# Schematic.net
KiCad netlist of a schematic drawn in EasyEDA
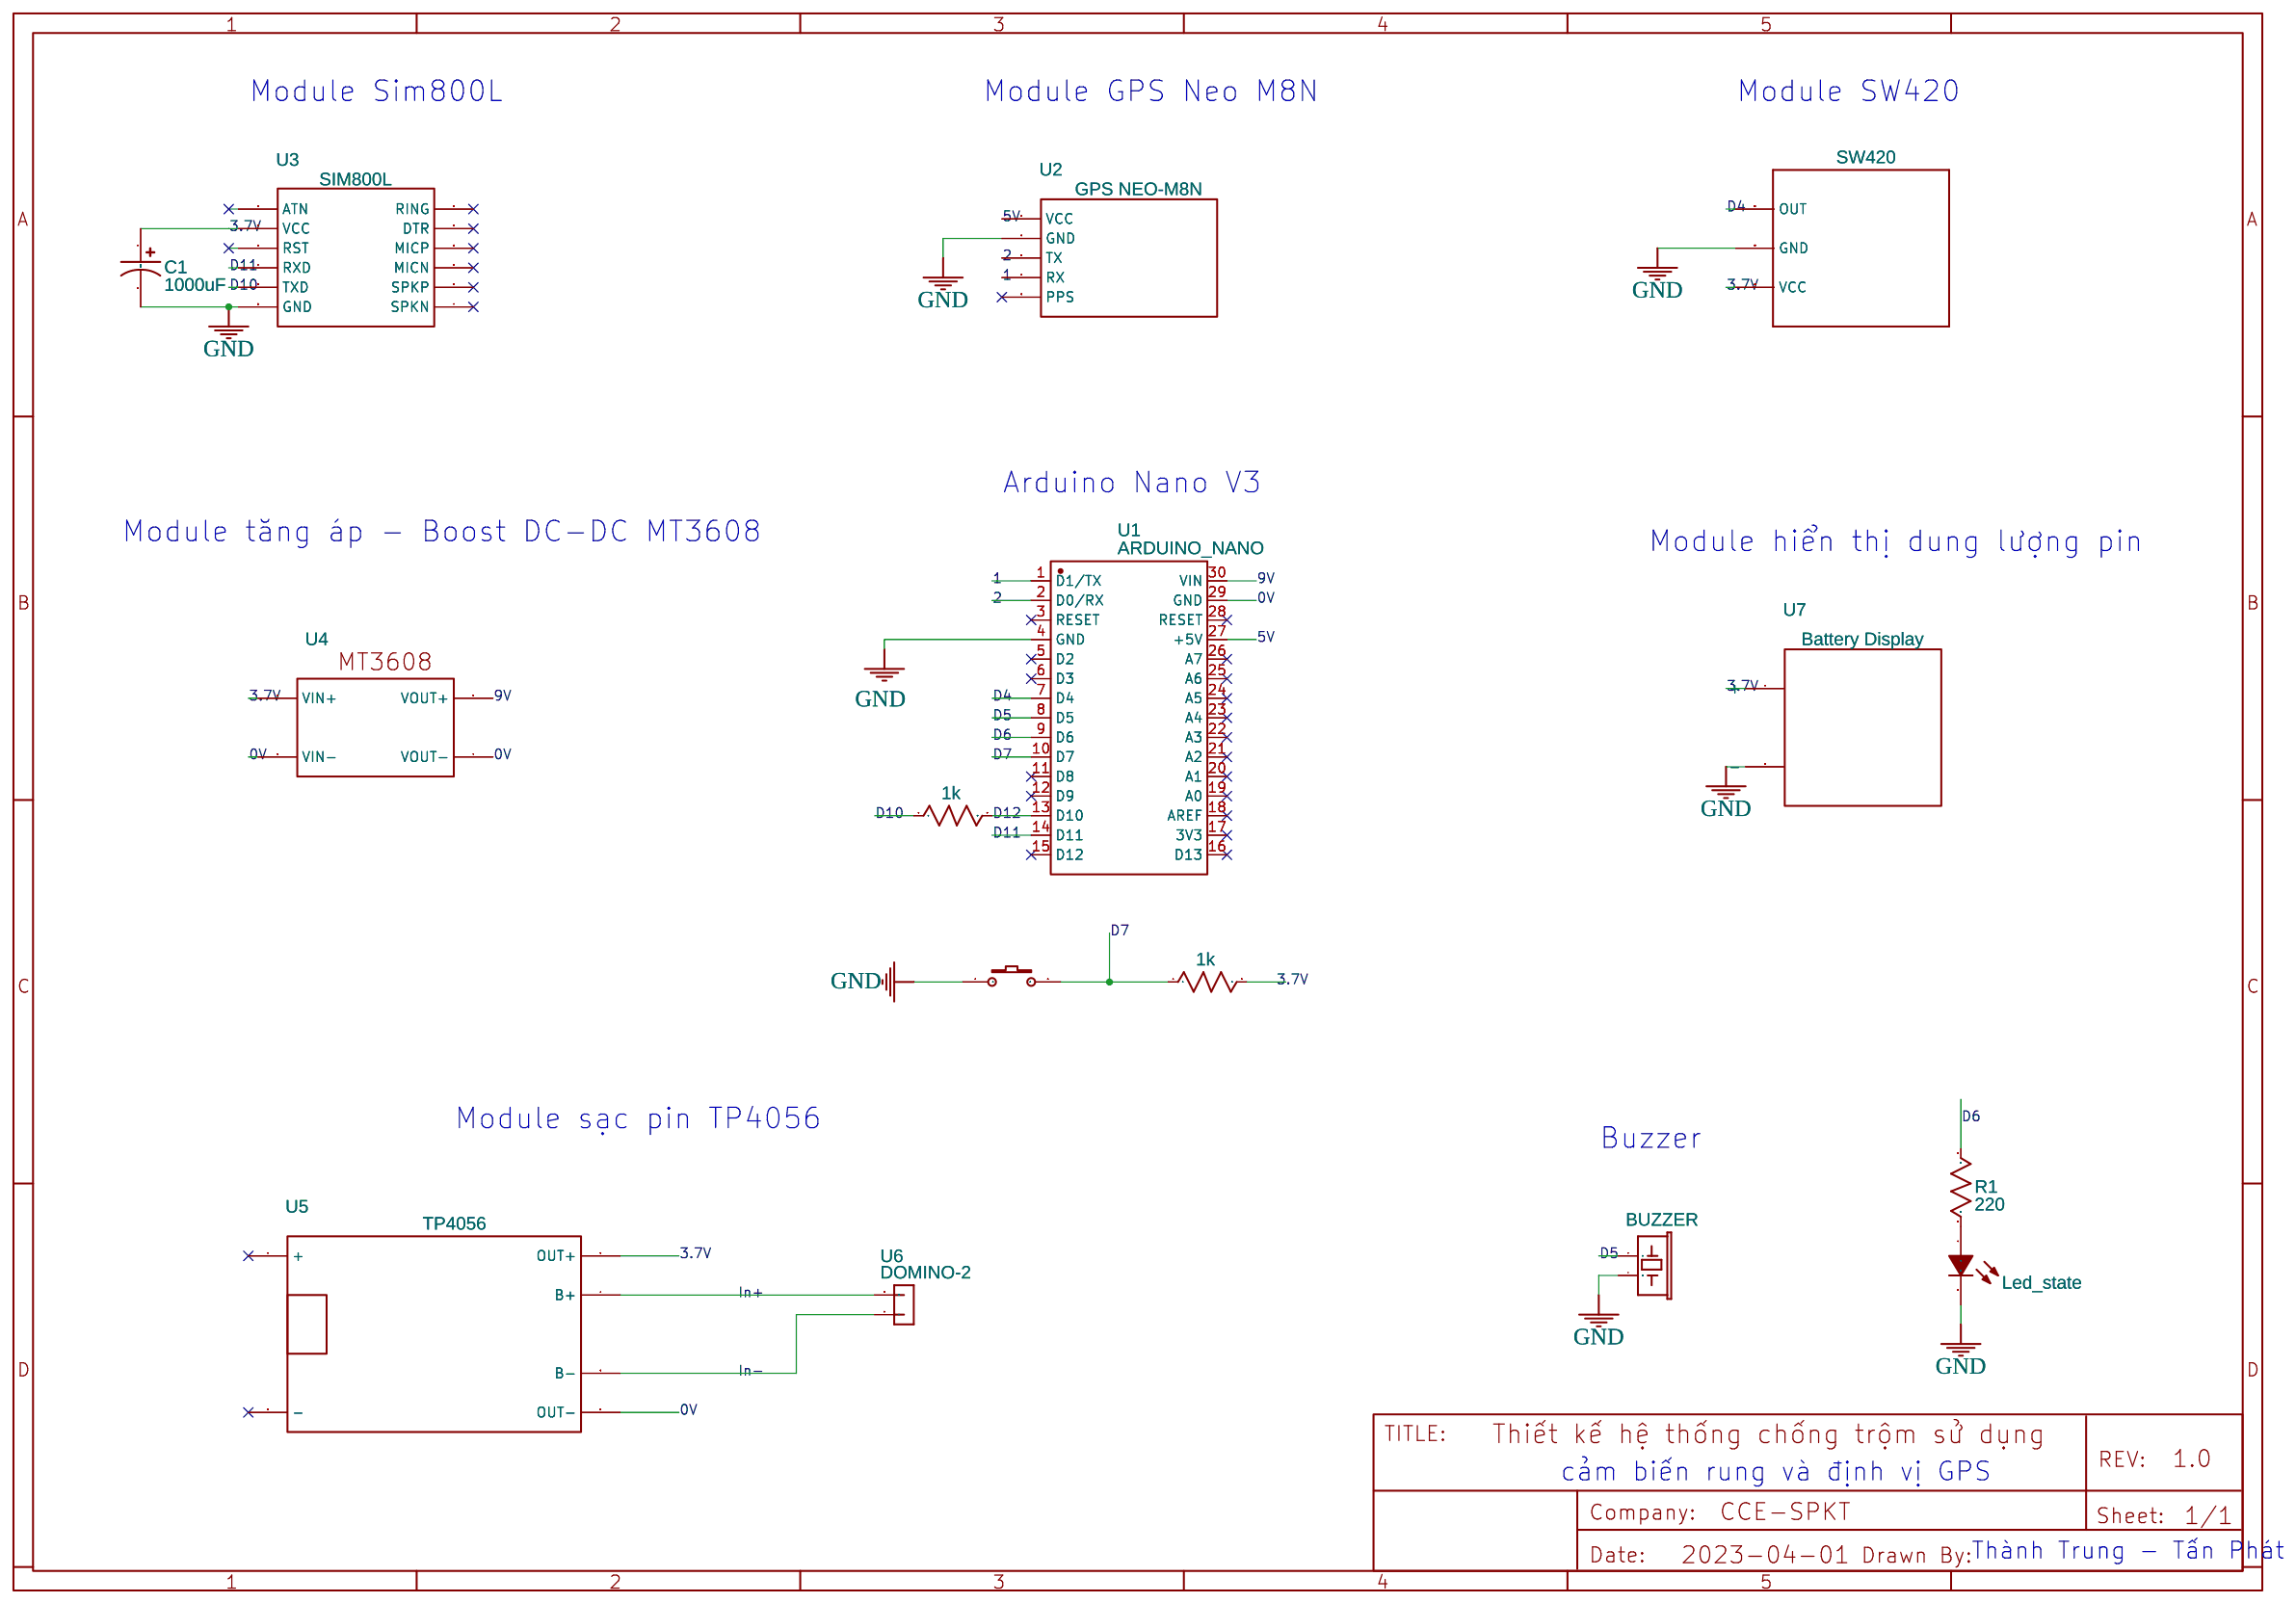
[diagram p0: schematic sheet]

(export (version "E")
  (design (tool "Eeschema 10.0.6"))
  (components
    (comp (ref "1") (value "SW420") (libsource (lib "") (part "SW420")))
    (comp (ref "C1")
      (value "1000uF")
      (fields
        (field (name "BOM_Manufacturer Part") "SHW1000UF6.3V6.3X11")
        (field (name "BOM_Supplier Part") "C494544")
      )
      (libsource (lib "") (part "SHW1000UF6.3V6.3X11"))
    )
    (comp (ref "KEY1")
      (value "K2-3.6×6.1_SMD")
      (fields
        (field (name "BOM_Manufacturer Part") "K2-1107ST-A4SW-06")
        (field (name "BOM_Supplier Part") "C118141")
      )
      (libsource (lib "") (part "K2-3.6×6.1_SMD"))
    )
    (comp (ref "LED1")
      (value "Led_state")
      (fields
        (field (name "BOM_Manufacturer Part") "LED_5MM")
        (field (name "BOM_Supplier Part") "C9900023552")
      )
      (libsource (lib "") (part "LED_5MM"))
    )
    (comp (ref "R1") (value "220") (libsource (lib "") (part "R_0603_US")))
    (comp (ref "R2") (value "1k") (libsource (lib "") (part "R_0603_US_1")))
    (comp (ref "R3") (value "1k") (libsource (lib "") (part "R_0603_US_1")))
    (comp (ref "SG1") (value "BUZZER") (libsource (lib "") (part "BUZZERPTH-NS-KIT")))
    (comp (ref "U1")
      (value "ARDUINO_NANO")
      (fields (field (name "BOM_Supplier Part") "C9900017879"))
      (libsource (lib "") (part "ARDUINO_NANO"))
    )
    (comp (ref "U2") (value "GPS NEO-M8N") (libsource (lib "") (part "NEO-M8N Double Sided GPS Mini Module")))
    (comp (ref "U3") (value "SIM800L") (libsource (lib "") (part "SIM800L_MODULE")))
    (comp (ref "U4") (value "MT3608") (libsource (lib "") (part "MT3608")))
    (comp (ref "U5") (value "TP4056") (libsource (lib "") (part "TP4056 MODULE")))
    (comp (ref "U6") (value "DOMINO-2") (libsource (lib "") (part "DOMINO-2")))
    (comp (ref "U7")
      (value "Battery Display")
      (fields (field (name "BOM_Manufacturer Part") "540-563"))
      (libsource (lib "") (part "báo pin"))
    )
  )
  (nets
    (net (code "1") (name "/0V") (class "Default")
      (node (ref "U1") (pin "29") (pinfunction "GND_29") (pintype "unspecified"))
      (node (ref "U4") (pin "2") (pinfunction "VIN-_2") (pintype "unspecified"))
      (node (ref "U4") (pin "4") (pinfunction "VOUT-_4") (pintype "unspecified"))
      (node (ref "U5") (pin "6") (pinfunction "OUT-_6") (pintype "unspecified"))
    )
    (net (code "2") (name "/1") (class "Default")
      (node (ref "U1") (pin "1") (pinfunction "D1/TX_1") (pintype "unspecified"))
      (node (ref "U2") (pin "4") (pinfunction "RX_4") (pintype "unspecified"))
    )
    (net (code "3") (name "/2") (class "Default")
      (node (ref "U1") (pin "2") (pinfunction "D0/RX_2") (pintype "unspecified"))
      (node (ref "U2") (pin "3") (pinfunction "TX_3") (pintype "unspecified"))
    )
    (net (code "4") (name "/3.7V") (class "Default")
      (node (ref "1") (pin "VCC") (pinfunction "VCC_VCC") (pintype "bidirectional"))
      (node (ref "C1") (pin "1") (pinfunction "1_1") (pintype "unspecified"))
      (node (ref "R2") (pin "2") (pinfunction "2_2") (pintype "unspecified"))
      (node (ref "U3") (pin "2") (pinfunction "VCC_2") (pintype "unspecified"))
      (node (ref "U4") (pin "1") (pinfunction "VIN+_1") (pintype "unspecified"))
      (node (ref "U5") (pin "3") (pinfunction "OUT+_3") (pintype "unspecified"))
      (node (ref "U7") (pin "1") (pinfunction "+_1") (pintype "unspecified"))
    )
    (net (code "5") (name "/5V") (class "Default")
      (node (ref "U1") (pin "27") (pinfunction "+5V_27") (pintype "unspecified"))
      (node (ref "U2") (pin "1") (pinfunction "VCC_1") (pintype "unspecified"))
    )
    (net (code "6") (name "/9V") (class "Default")
      (node (ref "U1") (pin "30") (pinfunction "VIN_30") (pintype "unspecified"))
      (node (ref "U4") (pin "3") (pinfunction "VOUT+_3") (pintype "unspecified"))
    )
    (net (code "7") (name "/D4") (class "Default")
      (node (ref "1") (pin "OUT") (pinfunction "OUT_OUT") (pintype "bidirectional"))
      (node (ref "U1") (pin "7") (pinfunction "D4_7") (pintype "unspecified"))
    )
    (net (code "8") (name "/D5") (class "Default")
      (node (ref "SG1") (pin "+") (pinfunction "1_+") (pintype "unspecified"))
      (node (ref "U1") (pin "8") (pinfunction "D5_8") (pintype "unspecified"))
    )
    (net (code "9") (name "/D6") (class "Default")
      (node (ref "R1") (pin "1") (pinfunction "1_1") (pintype "unspecified"))
      (node (ref "U1") (pin "9") (pinfunction "D6_9") (pintype "unspecified"))
    )
    (net (code "10") (name "/D7") (class "Default")
      (node (ref "KEY1") (pin "2") (pinfunction "2_2") (pintype "unspecified"))
      (node (ref "R2") (pin "1") (pinfunction "1_1") (pintype "unspecified"))
      (node (ref "U1") (pin "10") (pinfunction "D7_10") (pintype "unspecified"))
    )
    (net (code "11") (name "/D10") (class "Default")
      (node (ref "R3") (pin "1") (pinfunction "1_1") (pintype "unspecified"))
      (node (ref "U3") (pin "5") (pinfunction "TXD_5") (pintype "unspecified"))
    )
    (net (code "12") (name "/D11") (class "Default")
      (node (ref "U1") (pin "14") (pinfunction "D11_14") (pintype "unspecified"))
      (node (ref "U3") (pin "4") (pinfunction "RXD_4") (pintype "unspecified"))
    )
    (net (code "13") (name "/D12") (class "Default")
      (node (ref "R3") (pin "2") (pinfunction "2_2") (pintype "unspecified"))
      (node (ref "U1") (pin "13") (pinfunction "D10_13") (pintype "unspecified"))
    )
    (net (code "14") (name "/In+") (class "Default")
      (node (ref "U5") (pin "4") (pinfunction "B+_4") (pintype "unspecified"))
      (node (ref "U6") (pin "2") (pinfunction "2_2") (pintype "unspecified"))
    )
    (net (code "15") (name "/In-") (class "Default")
      (node (ref "U5") (pin "5") (pinfunction "B-_5") (pintype "unspecified"))
      (node (ref "U6") (pin "1") (pinfunction "1_1") (pintype "unspecified"))
    )
    (net (code "16") (name "GND") (class "Default")
      (node (ref "1") (pin "GND") (pinfunction "GND_GND") (pintype "bidirectional"))
      (node (ref "C1") (pin "2") (pinfunction "2_2") (pintype "unspecified"))
      (node (ref "KEY1") (pin "1") (pinfunction "1_1") (pintype "unspecified"))
      (node (ref "LED1") (pin "2") (pinfunction "K_2") (pintype "input"))
      (node (ref "SG1") (pin "-") (pinfunction "2_-") (pintype "unspecified"))
      (node (ref "U1") (pin "4") (pinfunction "GND_4") (pintype "unspecified"))
      (node (ref "U2") (pin "2") (pinfunction "GND_2") (pintype "unspecified"))
      (node (ref "U3") (pin "6") (pinfunction "GND_6") (pintype "unspecified"))
      (node (ref "U7") (pin "2") (pinfunction "-_2") (pintype "unspecified"))
    )
    (net (code "17") (name "Net-(LED1-A)") (class "Default")
      (node (ref "LED1") (pin "1") (pinfunction "A_1") (pintype "input"))
      (node (ref "R1") (pin "2") (pinfunction "2_2") (pintype "unspecified"))
    )
    (net (code "18") (name "unconnected-(U1-3V3-Pad17)") (class "Default")
      (node (ref "U1") (pin "17") (pinfunction "3V3_17") (pintype "unspecified+no_connect"))
    )
    (net (code "19") (name "unconnected-(U1-A0-Pad19)") (class "Default")
      (node (ref "U1") (pin "19") (pinfunction "A0_19") (pintype "unspecified+no_connect"))
    )
    (net (code "20") (name "unconnected-(U1-A1-Pad20)") (class "Default")
      (node (ref "U1") (pin "20") (pinfunction "A1_20") (pintype "unspecified+no_connect"))
    )
    (net (code "21") (name "unconnected-(U1-A2-Pad21)") (class "Default")
      (node (ref "U1") (pin "21") (pinfunction "A2_21") (pintype "unspecified+no_connect"))
    )
    (net (code "22") (name "unconnected-(U1-A3-Pad22)") (class "Default")
      (node (ref "U1") (pin "22") (pinfunction "A3_22") (pintype "unspecified+no_connect"))
    )
    (net (code "23") (name "unconnected-(U1-A4-Pad23)") (class "Default")
      (node (ref "U1") (pin "23") (pinfunction "A4_23") (pintype "unspecified+no_connect"))
    )
    (net (code "24") (name "unconnected-(U1-A5-Pad24)") (class "Default")
      (node (ref "U1") (pin "24") (pinfunction "A5_24") (pintype "unspecified+no_connect"))
    )
    (net (code "25") (name "unconnected-(U1-A6-Pad25)") (class "Default")
      (node (ref "U1") (pin "25") (pinfunction "A6_25") (pintype "unspecified+no_connect"))
    )
    (net (code "26") (name "unconnected-(U1-A7-Pad26)") (class "Default")
      (node (ref "U1") (pin "26") (pinfunction "A7_26") (pintype "unspecified+no_connect"))
    )
    (net (code "27") (name "unconnected-(U1-AREF-Pad18)") (class "Default")
      (node (ref "U1") (pin "18") (pinfunction "AREF_18") (pintype "unspecified+no_connect"))
    )
    (net (code "28") (name "unconnected-(U1-D2-Pad5)") (class "Default")
      (node (ref "U1") (pin "5") (pinfunction "D2_5") (pintype "unspecified+no_connect"))
    )
    (net (code "29") (name "unconnected-(U1-D3-Pad6)") (class "Default")
      (node (ref "U1") (pin "6") (pinfunction "D3_6") (pintype "unspecified+no_connect"))
    )
    (net (code "30") (name "unconnected-(U1-D8-Pad11)") (class "Default")
      (node (ref "U1") (pin "11") (pinfunction "D8_11") (pintype "unspecified+no_connect"))
    )
    (net (code "31") (name "unconnected-(U1-D9-Pad12)") (class "Default")
      (node (ref "U1") (pin "12") (pinfunction "D9_12") (pintype "unspecified+no_connect"))
    )
    (net (code "32") (name "unconnected-(U1-D12-Pad15)") (class "Default")
      (node (ref "U1") (pin "15") (pinfunction "D12_15") (pintype "unspecified+no_connect"))
    )
    (net (code "33") (name "unconnected-(U1-D13-Pad16)") (class "Default")
      (node (ref "U1") (pin "16") (pinfunction "D13_16") (pintype "unspecified+no_connect"))
    )
    (net (code "34") (name "unconnected-(U1-RESET-Pad3)") (class "Default")
      (node (ref "U1") (pin "3") (pinfunction "RESET_3") (pintype "unspecified+no_connect"))
    )
    (net (code "35") (name "unconnected-(U1-RESET-Pad28)") (class "Default")
      (node (ref "U1") (pin "28") (pinfunction "RESET_28") (pintype "unspecified+no_connect"))
    )
    (net (code "36") (name "unconnected-(U2-PPS-Pad5)") (class "Default")
      (node (ref "U2") (pin "5") (pinfunction "PPS_5") (pintype "unspecified+no_connect"))
    )
    (net (code "37") (name "unconnected-(U3-ATN-Pad1)") (class "Default")
      (node (ref "U3") (pin "1") (pinfunction "ATN_1") (pintype "unspecified+no_connect"))
    )
    (net (code "38") (name "unconnected-(U3-DTR-Pad11)") (class "Default")
      (node (ref "U3") (pin "11") (pinfunction "DTR_11") (pintype "unspecified+no_connect"))
    )
    (net (code "39") (name "unconnected-(U3-MICN-Pad9)") (class "Default")
      (node (ref "U3") (pin "9") (pinfunction "MICN_9") (pintype "unspecified+no_connect"))
    )
    (net (code "40") (name "unconnected-(U3-MICP-Pad10)") (class "Default")
      (node (ref "U3") (pin "10") (pinfunction "MICP_10") (pintype "unspecified+no_connect"))
    )
    (net (code "41") (name "unconnected-(U3-RING-Pad12)") (class "Default")
      (node (ref "U3") (pin "12") (pinfunction "RING_12") (pintype "unspecified+no_connect"))
    )
    (net (code "42") (name "unconnected-(U3-RST-Pad3)") (class "Default")
      (node (ref "U3") (pin "3") (pinfunction "RST_3") (pintype "unspecified+no_connect"))
    )
    (net (code "43") (name "unconnected-(U3-SPKN-Pad7)") (class "Default")
      (node (ref "U3") (pin "7") (pinfunction "SPKN_7") (pintype "unspecified+no_connect"))
    )
    (net (code "44") (name "unconnected-(U3-SPKP-Pad8)") (class "Default")
      (node (ref "U3") (pin "8") (pinfunction "SPKP_8") (pintype "unspecified+no_connect"))
    )
    (net (code "45") (name "unconnected-(U5-+-Pad1)") (class "Default")
      (node (ref "U5") (pin "1") (pinfunction "+_1") (pintype "unspecified+no_connect"))
    )
    (net (code "46") (name "unconnected-(U5---Pad2)") (class "Default")
      (node (ref "U5") (pin "2") (pinfunction "-_2") (pintype "unspecified+no_connect"))
    )
  )
)
